# Sheet1.net
KiCad netlist of a schematic drawn in Altium Designer
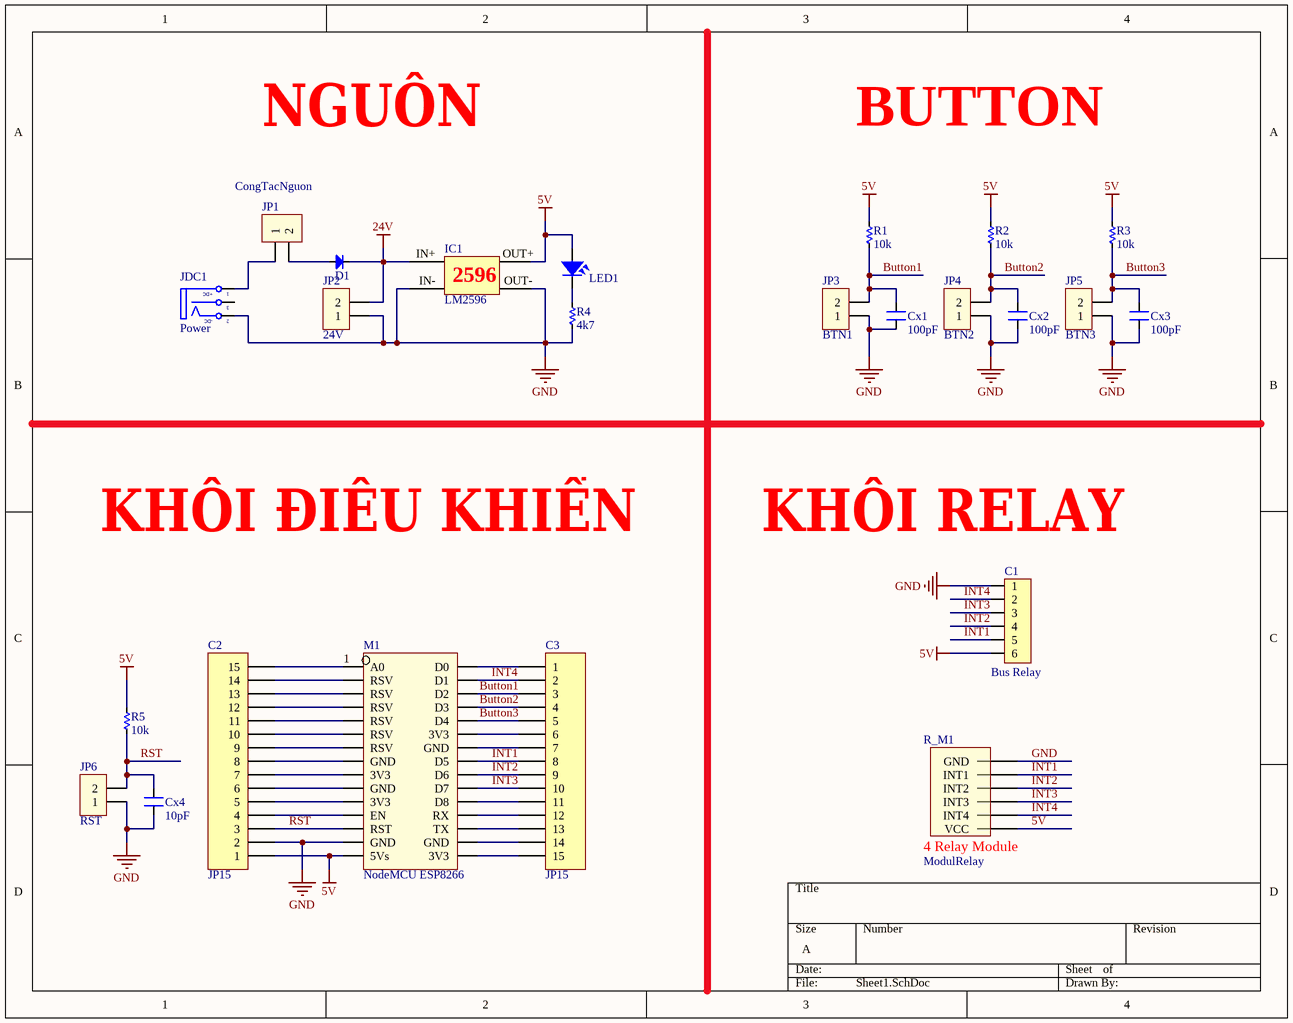
[diagram p0: Sheet1.SchDoc]

(export (version "E")
  (design (tool "Eeschema 10.0.6"))
  (components
    (comp (ref "C1")
      (value "Bus Relay")
      (footprint "Header6")
      (description "Header IDC, 6 x 1 Pin Vertical 2.54mm Pitch (Non-Boxed, Male)")
      (fields
        (field (name "MANUFACTURER") "Würth Elektronik eiSos GmbH")
        (field (name "PARTNO") "613002143121")
        (field (name "CREATED BY") "Karrer Zheng")
      )
      (libsource (lib "LIBRARY") (part "Header6"))
    )
    (comp (ref "C2")
      (value "JP15")
      (footprint "JP15-C1T")
      (description "WR-PHD 2.54 mm Angled Socket Header")
      (fields
        (field (name "MANUFACTURER") "Würth Elektronik eiSos GmbH")
        (field (name "PARTNO") "613015143121")
        (field (name "CREATED BY") "Karrer Zheng")
      )
      (libsource (lib "LIBRARY") (part "JP15"))
    )
    (comp (ref "C3")
      (value "JP15")
      (footprint "JP15-C1T")
      (description "WR-PHD 2.54 mm Angled Socket Header")
      (fields
        (field (name "MANUFACTURER") "Würth Elektronik eiSos GmbH")
        (field (name "PARTNO") "613015143121")
        (field (name "CREATED BY") "Karrer Zheng")
      )
      (libsource (lib "") (part "JP15_1"))
    )
    (comp (ref "Cx1") (value "100pF") (footprint "CN1.5") (libsource (lib "LIBRARY") (part "CN")))
    (comp (ref "Cx2") (value "100pF") (footprint "CN1.5") (libsource (lib "LIBRARY") (part "CN")))
    (comp (ref "Cx3") (value "100pF") (footprint "CN1.5") (libsource (lib "LIBRARY") (part "CN")))
    (comp (ref "Cx4") (value "10pF") (footprint "CN1.5") (libsource (lib "LIBRARY") (part "CN")))
    (comp (ref "D1")
      (value "Diode")
      (footprint "DIO-5A")
      (description "Default Diode")
      (fields (field (name "PUBLISHER") "Altium Limited"))
      (libsource (lib "LIBRARY") (part "Diode"))
    )
    (comp (ref "IC1")
      (value "LM2596")
      (footprint "LM2596")
      (libsource (lib "LIBERARY_TIENDAT") (part "LM2596"))
    )
    (comp (ref "JDC1")
      (value "Power")
      (footprint "DC0")
      (description "Jac DC input")
      (libsource (lib "LIBRARY") (part "DCIN"))
    )
    (comp (ref "JP1")
      (value "CongTacNguon")
      (footprint "Header-2P")
      (libsource (lib "") (part "Header-2P_1"))
    )
    (comp (ref "JP2")
      (value "24V")
      (footprint "Header-2P")
      (libsource (lib "LIBERARY_TIENDAT") (part "Header-2P"))
    )
    (comp (ref "JP3")
      (value "BTN1")
      (footprint "Header-2P")
      (libsource (lib "LIBERARY_TIENDAT") (part "Header-2P"))
    )
    (comp (ref "JP4")
      (value "BTN2")
      (footprint "Header-2P")
      (libsource (lib "LIBERARY_TIENDAT") (part "Header-2P"))
    )
    (comp (ref "JP5")
      (value "BTN3")
      (footprint "Header-2P")
      (libsource (lib "LIBERARY_TIENDAT") (part "Header-2P"))
    )
    (comp (ref "JP6")
      (value "RST")
      (footprint "Header-2P")
      (libsource (lib "LIBERARY_TIENDAT") (part "Header-2P"))
    )
    (comp (ref "LED1")
      (value "LED")
      (footprint "LED-3MM-YELLOW")
      (description "LED Single colour Green and Red")
      (libsource (lib "LIBRARY") (part "LED"))
    )
    (comp (ref "M1")
      (value "NodeMCU ESP8266")
      (footprint "NodeMCU ESP8266")
      (libsource (lib "NodeMCU ESP8266") (part "NodeMCU ESP8266"))
    )
    (comp (ref "R1")
      (value "10k")
      (footprint "RES-1/4W")
      (description "Res")
      (fields
        (field (name "MANUFACTURER") "Generic Components")
        (field (name "PUBLISHER") "Altium Hobart Technology Centre")
      )
      (libsource (lib "LIBRARY") (part "Res"))
    )
    (comp (ref "R2")
      (value "10k")
      (footprint "RES-1/4W")
      (description "Res")
      (fields
        (field (name "MANUFACTURER") "Generic Components")
        (field (name "PUBLISHER") "Altium Hobart Technology Centre")
      )
      (libsource (lib "LIBRARY") (part "Res"))
    )
    (comp (ref "R3")
      (value "10k")
      (footprint "RES-1/4W")
      (description "Res")
      (fields
        (field (name "MANUFACTURER") "Generic Components")
        (field (name "PUBLISHER") "Altium Hobart Technology Centre")
      )
      (libsource (lib "LIBRARY") (part "Res"))
    )
    (comp (ref "R4")
      (value "4k7")
      (footprint "RES-1/8WD")
      (description "Res")
      (fields
        (field (name "MANUFACTURER") "Generic Components")
        (field (name "PUBLISHER") "Altium Hobart Technology Centre")
      )
      (libsource (lib "LIBRARY") (part "Res"))
    )
    (comp (ref "R5")
      (value "10k")
      (footprint "RES-1/4W")
      (description "Res")
      (fields
        (field (name "MANUFACTURER") "Generic Components")
        (field (name "PUBLISHER") "Altium Hobart Technology Centre")
      )
      (libsource (lib "LIBRARY") (part "Res"))
    )
    (comp (ref "R_M1")
      (value "ModulRelay")
      (footprint "Relay_4_Modul")
      (libsource (lib "LIBERARY_TIENDAT") (part "Modul_Relay_4Chan"))
    )
  )
  (nets
    (net (code "1") (name "/Button1") (class "Default")
      (node (ref "C3") (pin "3") (pinfunction "3_3") (pintype "passive"))
      (node (ref "Cx1") (pin "2") (pinfunction "2_2") (pintype "passive"))
      (node (ref "JP3") (pin "2") (pinfunction "2_2") (pintype "passive"))
      (node (ref "M1") (pin "28") (pinfunction "D2_28") (pintype "passive"))
      (node (ref "R1") (pin "2") (pinfunction "2_2") (pintype "passive"))
    )
    (net (code "2") (name "/Button2") (class "Default")
      (node (ref "C3") (pin "4") (pinfunction "4_4") (pintype "passive"))
      (node (ref "Cx2") (pin "2") (pinfunction "2_2") (pintype "passive"))
      (node (ref "JP4") (pin "2") (pinfunction "2_2") (pintype "passive"))
      (node (ref "M1") (pin "27") (pinfunction "D3_27") (pintype "passive"))
      (node (ref "R2") (pin "2") (pinfunction "2_2") (pintype "passive"))
    )
    (net (code "3") (name "/Button3") (class "Default")
      (node (ref "C3") (pin "5") (pinfunction "5_5") (pintype "passive"))
      (node (ref "Cx3") (pin "2") (pinfunction "2_2") (pintype "passive"))
      (node (ref "JP5") (pin "2") (pinfunction "2_2") (pintype "passive"))
      (node (ref "M1") (pin "26") (pinfunction "D4_26") (pintype "passive"))
      (node (ref "R3") (pin "2") (pinfunction "2_2") (pintype "passive"))
    )
    (net (code "4") (name "/INT1") (class "Default")
      (node (ref "C1") (pin "5") (pinfunction "5_5") (pintype "passive"))
      (node (ref "C3") (pin "8") (pinfunction "8_8") (pintype "passive"))
      (node (ref "M1") (pin "23") (pinfunction "D5_23") (pintype "passive"))
      (node (ref "R_M1") (pin "5") (pinfunction "INT1_5") (pintype "passive"))
    )
    (net (code "5") (name "/INT2") (class "Default")
      (node (ref "C1") (pin "4") (pinfunction "4_4") (pintype "passive"))
      (node (ref "C3") (pin "9") (pinfunction "9_9") (pintype "passive"))
      (node (ref "M1") (pin "22") (pinfunction "D6_22") (pintype "passive"))
      (node (ref "R_M1") (pin "4") (pinfunction "INT2_4") (pintype "passive"))
    )
    (net (code "6") (name "/INT3") (class "Default")
      (node (ref "C1") (pin "3") (pinfunction "3_3") (pintype "passive"))
      (node (ref "C3") (pin "10") (pinfunction "10_10") (pintype "passive"))
      (node (ref "M1") (pin "21") (pinfunction "D7_21") (pintype "passive"))
      (node (ref "R_M1") (pin "3") (pinfunction "INT3_3") (pintype "passive"))
    )
    (net (code "7") (name "/INT4") (class "Default")
      (node (ref "C1") (pin "2") (pinfunction "2_2") (pintype "passive"))
      (node (ref "C3") (pin "2") (pinfunction "2_2") (pintype "passive"))
      (node (ref "M1") (pin "29") (pinfunction "D1_29") (pintype "passive"))
      (node (ref "R_M1") (pin "2") (pinfunction "INT4_2") (pintype "passive"))
    )
    (net (code "8") (name "/RST") (class "Default")
      (node (ref "C2") (pin "3") (pinfunction "3_3") (pintype "passive"))
      (node (ref "Cx4") (pin "2") (pinfunction "2_2") (pintype "passive"))
      (node (ref "JP6") (pin "2") (pinfunction "2_2") (pintype "passive"))
      (node (ref "M1") (pin "13") (pinfunction "RST_13") (pintype "passive"))
      (node (ref "R5") (pin "2") (pinfunction "2_2") (pintype "passive"))
    )
    (net (code "9") (name "5V") (class "Default")
      (node (ref "C1") (pin "6") (pinfunction "6_6") (pintype "passive"))
      (node (ref "C2") (pin "1") (pinfunction "1_1") (pintype "passive"))
      (node (ref "IC1") (pin "OUT+") (pinfunction "OUT+_OUT+") (pintype "passive"))
      (node (ref "LED1") (pin "1") (pinfunction "1_1") (pintype "passive"))
      (node (ref "M1") (pin "15") (pinfunction "5Vs_15") (pintype "passive"))
      (node (ref "R1") (pin "1") (pinfunction "1_1") (pintype "passive"))
      (node (ref "R2") (pin "1") (pinfunction "1_1") (pintype "passive"))
      (node (ref "R3") (pin "1") (pinfunction "1_1") (pintype "passive"))
      (node (ref "R5") (pin "1") (pinfunction "1_1") (pintype "passive"))
      (node (ref "R_M1") (pin "1") (pinfunction "VCC_1") (pintype "passive"))
    )
    (net (code "10") (name "24V") (class "Default")
      (node (ref "D1") (pin "2") (pinfunction "K_2") (pintype "passive"))
      (node (ref "IC1") (pin "IN+") (pinfunction "IN+_IN+") (pintype "passive"))
      (node (ref "JP2") (pin "2") (pinfunction "2_2") (pintype "passive"))
    )
    (net (code "11") (name "GND") (class "Default")
      (node (ref "C1") (pin "1") (pinfunction "1_1") (pintype "passive"))
      (node (ref "C2") (pin "2") (pinfunction "2_2") (pintype "passive"))
      (node (ref "Cx1") (pin "1") (pinfunction "1_1") (pintype "passive"))
      (node (ref "Cx2") (pin "1") (pinfunction "1_1") (pintype "passive"))
      (node (ref "Cx3") (pin "1") (pinfunction "1_1") (pintype "passive"))
      (node (ref "Cx4") (pin "1") (pinfunction "1_1") (pintype "passive"))
      (node (ref "IC1") (pin "IN-") (pinfunction "IN-_IN-") (pintype "passive"))
      (node (ref "IC1") (pin "OUT-") (pinfunction "OUT-_OUT-") (pintype "passive"))
      (node (ref "JDC1") (pin "2") (pinfunction "TN_2") (pintype "passive"))
      (node (ref "JP2") (pin "1") (pinfunction "1_1") (pintype "passive"))
      (node (ref "JP3") (pin "1") (pinfunction "1_1") (pintype "passive"))
      (node (ref "JP4") (pin "1") (pinfunction "1_1") (pintype "passive"))
      (node (ref "JP5") (pin "1") (pinfunction "1_1") (pintype "passive"))
      (node (ref "JP6") (pin "1") (pinfunction "1_1") (pintype "passive"))
      (node (ref "M1") (pin "14") (pinfunction "GND_14") (pintype "passive"))
      (node (ref "R4") (pin "1") (pinfunction "1_1") (pintype "passive"))
      (node (ref "R_M1") (pin "6") (pinfunction "GND_6") (pintype "passive"))
    )
    (net (code "12") (name "Net-(C2-Pad5)") (class "Default")
      (node (ref "C2") (pin "5") (pinfunction "5_5") (pintype "passive"))
      (node (ref "M1") (pin "11") (pinfunction "3V3_11") (pintype "passive"))
    )
    (net (code "13") (name "Net-(C2-Pad6)") (class "Default")
      (node (ref "C2") (pin "6") (pinfunction "6_6") (pintype "passive"))
      (node (ref "M1") (pin "10") (pinfunction "GND_10") (pintype "passive"))
    )
    (net (code "14") (name "Net-(C2-Pad7)") (class "Default")
      (node (ref "C2") (pin "7") (pinfunction "7_7") (pintype "passive"))
      (node (ref "M1") (pin "9") (pinfunction "3V3_9") (pintype "passive"))
    )
    (net (code "15") (name "Net-(C2-Pad8)") (class "Default")
      (node (ref "C2") (pin "8") (pinfunction "8_8") (pintype "passive"))
      (node (ref "M1") (pin "8") (pinfunction "GND_8") (pintype "passive"))
    )
    (net (code "16") (name "Net-(C2-Pad9)") (class "Default")
      (node (ref "C2") (pin "9") (pinfunction "9_9") (pintype "passive"))
      (node (ref "M1") (pin "7") (pinfunction "RSV_7") (pintype "passive"))
    )
    (net (code "17") (name "Net-(C2-Pad10)") (class "Default")
      (node (ref "C2") (pin "10") (pinfunction "10_10") (pintype "passive"))
      (node (ref "M1") (pin "6") (pinfunction "RSV_6") (pintype "passive"))
    )
    (net (code "18") (name "Net-(C2-Pad11)") (class "Default")
      (node (ref "C2") (pin "11") (pinfunction "11_11") (pintype "passive"))
      (node (ref "M1") (pin "5") (pinfunction "RSV_5") (pintype "passive"))
    )
    (net (code "19") (name "Net-(C2-Pad12)") (class "Default")
      (node (ref "C2") (pin "12") (pinfunction "12_12") (pintype "passive"))
      (node (ref "M1") (pin "4") (pinfunction "RSV_4") (pintype "passive"))
    )
    (net (code "20") (name "Net-(C2-Pad13)") (class "Default")
      (node (ref "C2") (pin "13") (pinfunction "13_13") (pintype "passive"))
      (node (ref "M1") (pin "3") (pinfunction "RSV_3") (pintype "passive"))
    )
    (net (code "21") (name "Net-(C2-Pad14)") (class "Default")
      (node (ref "C2") (pin "14") (pinfunction "14_14") (pintype "passive"))
      (node (ref "M1") (pin "2") (pinfunction "RSV_2") (pintype "passive"))
    )
    (net (code "22") (name "Net-(C3-Pad6)") (class "Default")
      (node (ref "C3") (pin "6") (pinfunction "6_6") (pintype "passive"))
      (node (ref "M1") (pin "25") (pinfunction "3V3_25") (pintype "passive"))
    )
    (net (code "23") (name "Net-(C3-Pad7)") (class "Default")
      (node (ref "C3") (pin "7") (pinfunction "7_7") (pintype "passive"))
      (node (ref "M1") (pin "24") (pinfunction "GND_24") (pintype "passive"))
    )
    (net (code "24") (name "Net-(C3-Pad14)") (class "Default")
      (node (ref "C3") (pin "14") (pinfunction "14_14") (pintype "passive"))
      (node (ref "M1") (pin "17") (pinfunction "GND_17") (pintype "passive"))
    )
    (net (code "25") (name "Net-(C3-Pad15)") (class "Default")
      (node (ref "C3") (pin "15") (pinfunction "15_15") (pintype "passive"))
      (node (ref "M1") (pin "16") (pinfunction "3V3_16") (pintype "passive"))
    )
    (net (code "26") (name "Net-(D1-A)") (class "Default")
      (node (ref "D1") (pin "1") (pinfunction "A_1") (pintype "passive"))
      (node (ref "JP1") (pin "2") (pinfunction "2_2") (pintype "passive"))
    )
    (net (code "27") (name "Net-(JDC1-T)") (class "Default")
      (node (ref "JDC1") (pin "1") (pinfunction "T_1") (pintype "passive"))
      (node (ref "JP1") (pin "1") (pinfunction "1_1") (pintype "passive"))
    )
    (net (code "28") (name "Net-(LED1-Pad2)") (class "Default")
      (node (ref "LED1") (pin "2") (pinfunction "2_2") (pintype "passive"))
      (node (ref "R4") (pin "2") (pinfunction "2_2") (pintype "passive"))
    )
    (net (code "29") (name "Net-(M1-A0)") (class "Default")
      (node (ref "C2") (pin "15") (pinfunction "15_15") (pintype "passive"))
      (node (ref "M1") (pin "1") (pinfunction "A0_1") (pintype "passive"))
    )
    (net (code "30") (name "Net-(M1-D0)") (class "Default")
      (node (ref "C3") (pin "1") (pinfunction "1_1") (pintype "passive"))
      (node (ref "M1") (pin "30") (pinfunction "D0_30") (pintype "passive"))
    )
    (net (code "31") (name "Net-(M1-D8)") (class "Default")
      (node (ref "C3") (pin "11") (pinfunction "11_11") (pintype "passive"))
      (node (ref "M1") (pin "20") (pinfunction "D8_20") (pintype "passive"))
    )
    (net (code "32") (name "Net-(M1-EN)") (class "Default")
      (node (ref "C2") (pin "4") (pinfunction "4_4") (pintype "passive"))
      (node (ref "M1") (pin "12") (pinfunction "EN_12") (pintype "passive"))
    )
    (net (code "33") (name "Net-(M1-RX)") (class "Default")
      (node (ref "C3") (pin "12") (pinfunction "12_12") (pintype "passive"))
      (node (ref "M1") (pin "19") (pinfunction "RX_19") (pintype "passive"))
    )
    (net (code "34") (name "Net-(M1-TX)") (class "Default")
      (node (ref "C3") (pin "13") (pinfunction "13_13") (pintype "passive"))
      (node (ref "M1") (pin "18") (pinfunction "TX_18") (pintype "passive"))
    )
    (net (code "35") (name "unconnected-(JDC1-S-Pad3)") (class "Default")
      (node (ref "JDC1") (pin "3") (pinfunction "S_3") (pintype "power_in"))
    )
  )
)
